# LDO_sheet.net
KiCad netlist of a schematic drawn in Altium Designer
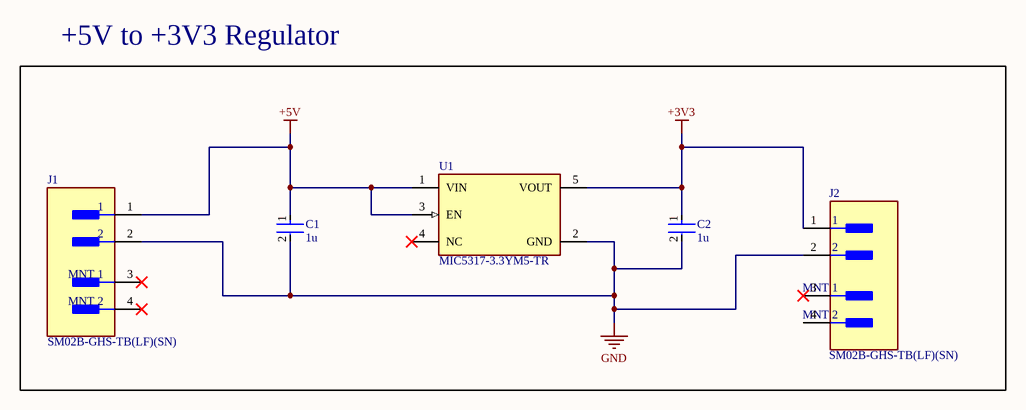
[diagram p0: LDO_sheet.SchDoc]

(export (version "E")
  (design (tool "Eeschema 10.0.6"))
  (components
    (comp (ref "C1")
      (value "1u")
      (footprint "FP-CC0805-0_85-MFG")
      (description "CAP CER 1UF 10V X7R 0805")
      (fields
        (field (name "MANUFACTURER") "Yageo")
        (field (name "OCTOPART") "https://octopart.com/cc0805kkx7r6bb105-yageo-42522859")
      )
      (libsource (lib "Altium Content Vault") (part "11868f565c42a9108669ba33697ecf6"))
    )
    (comp (ref "C2")
      (value "1u")
      (footprint "FP-CC0805-0_85-MFG")
      (description "CAP CER 1UF 10V X7R 0805")
      (fields
        (field (name "MANUFACTURER") "Yageo")
        (field (name "OCTOPART") "https://octopart.com/cc0805kkx7r6bb105-yageo-42522859")
      )
      (libsource (lib "Altium Content Vault") (part "11868f565c42a9108669ba33697ecf6"))
    )
    (comp (ref "J1")
      (value "SM02B-GHS-TB(LF)(SN)")
      (footprint "FP-SM02B-GHS-TB_LF_SN-MFG")
      (description "CONN HEADER SMD R/A 2POS 1.25MM")
      (libsource (lib "Altium Content Vault") (part "56ec3178a87b3978bdc1b3682cd516a"))
    )
    (comp (ref "J2")
      (value "SM02B-GHS-TB(LF)(SN)")
      (footprint "FP-SM02B-GHS-TB_LF_SN-MFG")
      (description "CONN HEADER SMD R/A 2POS 1.25MM")
      (libsource (lib "") (part "56ec3178a87b3978bdc1b3682cd516a_1"))
    )
    (comp (ref "U1")
      (value "MIC5317-3.3YM5-TR")
      (footprint "FP-SOT23-5LD-PL-1-MFG")
      (description "IC REG LINEAR 3.3V 150MA SOT23-5")
      (libsource (lib "Altium Content Vault") (part "0a093dae7315cdc977fd108dde87457"))
    )
  )
  (nets
    (net (code "1") (name "+3V3") (class "Default")
      (node (ref "C2") (pin "1") (pinfunction "1_1") (pintype "passive"))
      (node (ref "J2") (pin "1") (pinfunction "1_1") (pintype "passive"))
      (node (ref "U1") (pin "5") (pinfunction "VOUT_5") (pintype "power_in"))
    )
    (net (code "2") (name "+5V") (class "Default")
      (node (ref "C1") (pin "1") (pinfunction "1_1") (pintype "passive"))
      (node (ref "J1") (pin "1") (pinfunction "1_1") (pintype "passive"))
      (node (ref "U1") (pin "1") (pinfunction "VIN_1") (pintype "power_in"))
      (node (ref "U1") (pin "3") (pinfunction "EN_3") (pintype "input"))
    )
    (net (code "3") (name "GND") (class "Default")
      (node (ref "C1") (pin "2") (pinfunction "2_2") (pintype "passive"))
      (node (ref "C2") (pin "2") (pinfunction "2_2") (pintype "passive"))
      (node (ref "J1") (pin "2") (pinfunction "2_2") (pintype "passive"))
      (node (ref "J2") (pin "2") (pinfunction "2_2") (pintype "passive"))
      (node (ref "U1") (pin "2") (pinfunction "GND_2") (pintype "power_in"))
    )
    (net (code "4") (name "unconnected-(J1-MNT_1-Pad3)") (class "Default")
      (node (ref "J1") (pin "3") (pinfunction "MNT_1_3") (pintype "passive+no_connect"))
    )
    (net (code "5") (name "unconnected-(J1-MNT_2-Pad4)") (class "Default")
      (node (ref "J1") (pin "4") (pinfunction "MNT_2_4") (pintype "passive+no_connect"))
    )
    (net (code "6") (name "unconnected-(J2-MNT_1-Pad3)") (class "Default")
      (node (ref "J2") (pin "3") (pinfunction "MNT_1_3") (pintype "passive+no_connect"))
    )
    (net (code "7") (name "unconnected-(J2-MNT_2-Pad4)") (class "Default")
      (node (ref "J2") (pin "4") (pinfunction "MNT_2_4") (pintype "passive"))
    )
    (net (code "8") (name "unconnected-(U1-NC-Pad4)") (class "Default")
      (node (ref "U1") (pin "4") (pinfunction "NC_4") (pintype "passive+no_connect"))
    )
  )
)
